# untitled.net
KiCad netlist of a schematic drawn in EAGLE
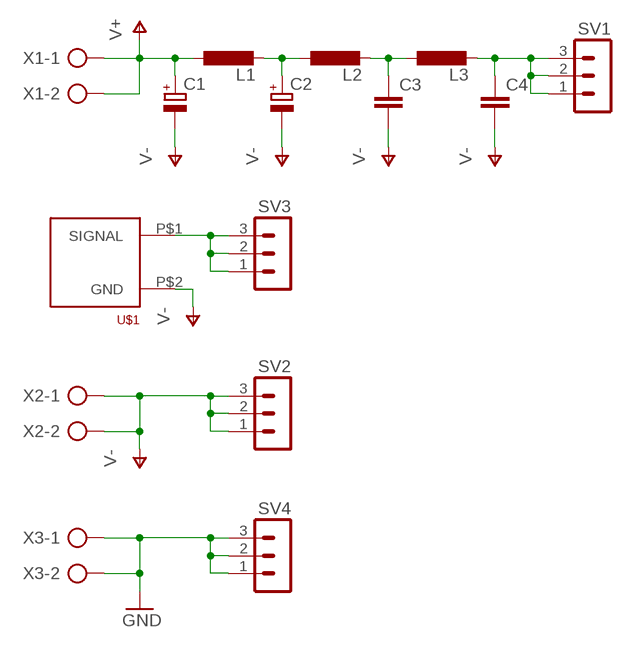
[diagram p0: schematic, sheet 1]

(export (version "E")
  (design (tool "Eeschema 10.0.6"))
  (components
    (comp (ref "C1")
      (value "CPOL-EUSMCA")
      (footprint "eagle-import:SMC_A")
      (libsource (lib "eagle-import") (part "CPOL-EUSMCA"))
    )
    (comp (ref "C2")
      (value "CPOL-EUSMCA")
      (footprint "eagle-import:SMC_A")
      (libsource (lib "eagle-import") (part "CPOL-EUSMCA"))
    )
    (comp (ref "C3")
      (value "C-EUC1206")
      (footprint "eagle-import:C1206")
      (libsource (lib "eagle-import") (part "C-EUC1206"))
    )
    (comp (ref "C4")
      (value "C-EUC1206")
      (footprint "eagle-import:C1206")
      (libsource (lib "eagle-import") (part "C-EUC1206"))
    )
    (comp (ref "L1")
      (value "L-EU0204/7")
      (footprint "eagle-import:0204_7")
      (libsource (lib "eagle-import") (part "L-EU0204/7"))
    )
    (comp (ref "L2")
      (value "L-EUL1812")
      (footprint "eagle-import:L1812")
      (libsource (lib "eagle-import") (part "L-EUL1812"))
    )
    (comp (ref "L3")
      (value "L-EUL1812")
      (footprint "eagle-import:L1812")
      (libsource (lib "eagle-import") (part "L-EUL1812"))
    )
    (comp (ref "SV1")
      (value "MA03-1")
      (footprint "eagle-import:MA03-1")
      (libsource (lib "eagle-import") (part "MA03-1"))
    )
    (comp (ref "SV2")
      (value "MA03-1")
      (footprint "eagle-import:MA03-1")
      (libsource (lib "eagle-import") (part "MA03-1"))
    )
    (comp (ref "SV3")
      (value "MA03-1")
      (footprint "eagle-import:MA03-1")
      (libsource (lib "eagle-import") (part "MA03-1"))
    )
    (comp (ref "SV4")
      (value "MA03-1")
      (footprint "eagle-import:MA03-1")
      (libsource (lib "eagle-import") (part "MA03-1"))
    )
    (comp (ref "U$1")
      (value "BNC_VERTICAL")
      (footprint "eagle-import:BNC_VERTICAL")
      (libsource (lib "eagle-import") (part "BNC_VERTICAL"))
    )
    (comp (ref "X1")
      (value "AK500/2-H")
      (footprint "eagle-import:AK500_2-H")
      (libsource (lib "eagle-import") (part "AK500/2-H"))
    )
    (comp (ref "X2")
      (value "AK500/2-H")
      (footprint "eagle-import:AK500_2-H")
      (libsource (lib "eagle-import") (part "AK500/2-H"))
    )
    (comp (ref "X3")
      (value "AK500/2-H")
      (footprint "eagle-import:AK500_2-H")
      (libsource (lib "eagle-import") (part "AK500/2-H"))
    )
  )
  (nets
    (net (code "1") (name "GND") (class "Default")
      (node (ref "SV4") (pin "1") (pinfunction "1_1") (pintype "passive"))
      (node (ref "SV4") (pin "2") (pinfunction "2_2") (pintype "passive"))
      (node (ref "SV4") (pin "3") (pinfunction "3_3") (pintype "passive"))
      (node (ref "X3") (pin "1") (pinfunction "KL_1") (pintype "passive"))
      (node (ref "X3") (pin "2") (pinfunction "KL_2") (pintype "passive"))
    )
    (net (code "2") (name "Net-(C2-Pad+)") (class "Default")
      (node (ref "C2") (pin "+") (pinfunction "+_+") (pintype "passive"))
      (node (ref "L1") (pin "2") (pinfunction "2_2") (pintype "passive"))
      (node (ref "L2") (pin "1") (pinfunction "1_1") (pintype "passive"))
    )
    (net (code "3") (name "Net-(C3-Pad1)") (class "Default")
      (node (ref "C3") (pin "1") (pinfunction "1_1") (pintype "passive"))
      (node (ref "L2") (pin "2") (pinfunction "2_2") (pintype "passive"))
      (node (ref "L3") (pin "1") (pinfunction "1_1") (pintype "passive"))
    )
    (net (code "4") (name "Net-(C4-Pad1)") (class "Default")
      (node (ref "C4") (pin "1") (pinfunction "1_1") (pintype "passive"))
      (node (ref "L3") (pin "2") (pinfunction "2_2") (pintype "passive"))
      (node (ref "SV1") (pin "1") (pinfunction "1_1") (pintype "passive"))
      (node (ref "SV1") (pin "2") (pinfunction "2_2") (pintype "passive"))
      (node (ref "SV1") (pin "3") (pinfunction "3_3") (pintype "passive"))
    )
    (net (code "5") (name "Net-(U$1-SIGNAL)") (class "Default")
      (node (ref "SV3") (pin "1") (pinfunction "1_1") (pintype "passive"))
      (node (ref "SV3") (pin "2") (pinfunction "2_2") (pintype "passive"))
      (node (ref "SV3") (pin "3") (pinfunction "3_3") (pintype "passive"))
      (node (ref "U$1") (pin "P$1") (pinfunction "SIGNAL_P$1") (pintype "bidirectional"))
    )
    (net (code "6") (name "V+") (class "Default")
      (node (ref "C1") (pin "+") (pinfunction "+_+") (pintype "passive"))
      (node (ref "L1") (pin "1") (pinfunction "1_1") (pintype "passive"))
      (node (ref "X1") (pin "1") (pinfunction "KL_1") (pintype "passive"))
      (node (ref "X1") (pin "2") (pinfunction "KL_2") (pintype "passive"))
    )
    (net (code "7") (name "V-") (class "Default")
      (node (ref "C1") (pin "-") (pinfunction "-_-") (pintype "passive"))
      (node (ref "C2") (pin "-") (pinfunction "-_-") (pintype "passive"))
      (node (ref "C3") (pin "2") (pinfunction "2_2") (pintype "passive"))
      (node (ref "C4") (pin "2") (pinfunction "2_2") (pintype "passive"))
      (node (ref "SV2") (pin "1") (pinfunction "1_1") (pintype "passive"))
      (node (ref "SV2") (pin "2") (pinfunction "2_2") (pintype "passive"))
      (node (ref "SV2") (pin "3") (pinfunction "3_3") (pintype "passive"))
      (node (ref "U$1") (pin "P$2") (pinfunction "GND_P$2") (pintype "bidirectional"))
      (node (ref "X2") (pin "1") (pinfunction "KL_1") (pintype "passive"))
      (node (ref "X2") (pin "2") (pinfunction "KL_2") (pintype "passive"))
    )
  )
)
